# board_2.net
KiCad netlist of a schematic drawn in EAGLE
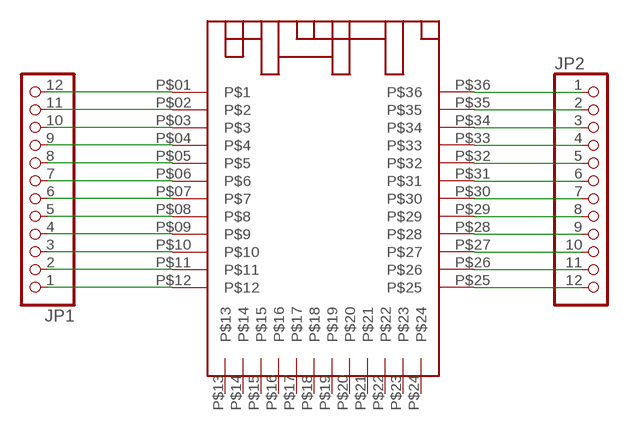
[diagram p0: schematic, sheet 1]

(export (version "E")
  (design (tool "Eeschema 10.0.6"))
  (components
    (comp (ref "JP1")
      (value "PINHD-1X12")
      (footprint "eagle-import:1X12")
      (libsource (lib "eagle-import") (part "PINHD-1X12"))
    )
    (comp (ref "JP2")
      (value "PINHD-1X12")
      (footprint "eagle-import:1X12")
      (libsource (lib "eagle-import") (part "PINHD-1X12"))
    )
    (comp (ref "U$1")
      (value "HZX_MODULE")
      (footprint "eagle-import:SMD_PAD_VERSION")
      (fields (field (name "AUTHOR") "Agam"))
      (libsource (lib "eagle-import") (part "HZX_MODULE"))
    )
  )
  (nets
    (net (code "1") (name "Net-(JP1-Pad1)") (class "Default")
      (node (ref "JP1") (pin "1") (pinfunction "1_1") (pintype "passive"))
      (node (ref "U$1") (pin "P$12") (pinfunction "P$12_P$12") (pintype "bidirectional"))
    )
    (net (code "2") (name "Net-(JP1-Pad2)") (class "Default")
      (node (ref "JP1") (pin "2") (pinfunction "2_2") (pintype "passive"))
      (node (ref "U$1") (pin "P$11") (pinfunction "P$11_P$11") (pintype "bidirectional"))
    )
    (net (code "3") (name "Net-(JP1-Pad3)") (class "Default")
      (node (ref "JP1") (pin "3") (pinfunction "3_3") (pintype "passive"))
      (node (ref "U$1") (pin "P$10") (pinfunction "P$10_P$10") (pintype "bidirectional"))
    )
    (net (code "4") (name "Net-(JP2-Pad1)") (class "Default")
      (node (ref "JP2") (pin "1") (pinfunction "1_1") (pintype "passive"))
      (node (ref "U$1") (pin "P$36") (pinfunction "P$36_P$36") (pintype "bidirectional"))
    )
    (net (code "5") (name "Net-(JP2-Pad2)") (class "Default")
      (node (ref "JP2") (pin "2") (pinfunction "2_2") (pintype "passive"))
      (node (ref "U$1") (pin "P$35") (pinfunction "P$35_P$35") (pintype "bidirectional"))
    )
    (net (code "6") (name "Net-(JP2-Pad3)") (class "Default")
      (node (ref "JP2") (pin "3") (pinfunction "3_3") (pintype "passive"))
      (node (ref "U$1") (pin "P$34") (pinfunction "P$34_P$34") (pintype "bidirectional"))
    )
    (net (code "7") (name "Net-(JP2-Pad4)") (class "Default")
      (node (ref "JP2") (pin "4") (pinfunction "4_4") (pintype "passive"))
      (node (ref "U$1") (pin "P$33") (pinfunction "P$33_P$33") (pintype "bidirectional"))
    )
    (net (code "8") (name "Net-(JP2-Pad5)") (class "Default")
      (node (ref "JP2") (pin "5") (pinfunction "5_5") (pintype "passive"))
      (node (ref "U$1") (pin "P$32") (pinfunction "P$32_P$32") (pintype "bidirectional"))
    )
    (net (code "9") (name "Net-(JP2-Pad6)") (class "Default")
      (node (ref "JP2") (pin "6") (pinfunction "6_6") (pintype "passive"))
      (node (ref "U$1") (pin "P$31") (pinfunction "P$31_P$31") (pintype "bidirectional"))
    )
    (net (code "10") (name "Net-(JP2-Pad7)") (class "Default")
      (node (ref "JP2") (pin "7") (pinfunction "7_7") (pintype "passive"))
      (node (ref "U$1") (pin "P$30") (pinfunction "P$30_P$30") (pintype "bidirectional"))
    )
    (net (code "11") (name "Net-(JP2-Pad8)") (class "Default")
      (node (ref "JP2") (pin "8") (pinfunction "8_8") (pintype "passive"))
      (node (ref "U$1") (pin "P$29") (pinfunction "P$29_P$29") (pintype "bidirectional"))
    )
    (net (code "12") (name "Net-(JP2-Pad9)") (class "Default")
      (node (ref "JP2") (pin "9") (pinfunction "9_9") (pintype "passive"))
      (node (ref "U$1") (pin "P$28") (pinfunction "P$28_P$28") (pintype "bidirectional"))
    )
    (net (code "13") (name "Net-(JP2-Pad10)") (class "Default")
      (node (ref "JP2") (pin "10") (pinfunction "10_10") (pintype "passive"))
      (node (ref "U$1") (pin "P$27") (pinfunction "P$27_P$27") (pintype "bidirectional"))
    )
    (net (code "14") (name "Net-(JP2-Pad11)") (class "Default")
      (node (ref "JP2") (pin "11") (pinfunction "11_11") (pintype "passive"))
      (node (ref "U$1") (pin "P$26") (pinfunction "P$26_P$26") (pintype "bidirectional"))
    )
    (net (code "15") (name "Net-(JP2-Pad12)") (class "Default")
      (node (ref "JP2") (pin "12") (pinfunction "12_12") (pintype "passive"))
      (node (ref "U$1") (pin "P$25") (pinfunction "P$25_P$25") (pintype "bidirectional"))
    )
    (net (code "16") (name "Net-(U$1-P$1)") (class "Default")
      (node (ref "JP1") (pin "12") (pinfunction "12_12") (pintype "passive"))
      (node (ref "U$1") (pin "P$01") (pinfunction "P$1_P$01") (pintype "bidirectional"))
    )
    (net (code "17") (name "Net-(U$1-P$2)") (class "Default")
      (node (ref "JP1") (pin "11") (pinfunction "11_11") (pintype "passive"))
      (node (ref "U$1") (pin "P$02") (pinfunction "P$2_P$02") (pintype "bidirectional"))
    )
    (net (code "18") (name "Net-(U$1-P$3)") (class "Default")
      (node (ref "JP1") (pin "10") (pinfunction "10_10") (pintype "passive"))
      (node (ref "U$1") (pin "P$03") (pinfunction "P$3_P$03") (pintype "bidirectional"))
    )
    (net (code "19") (name "Net-(U$1-P$4)") (class "Default")
      (node (ref "JP1") (pin "9") (pinfunction "9_9") (pintype "passive"))
      (node (ref "U$1") (pin "P$04") (pinfunction "P$4_P$04") (pintype "bidirectional"))
    )
    (net (code "20") (name "Net-(U$1-P$5)") (class "Default")
      (node (ref "JP1") (pin "8") (pinfunction "8_8") (pintype "passive"))
      (node (ref "U$1") (pin "P$05") (pinfunction "P$5_P$05") (pintype "bidirectional"))
    )
    (net (code "21") (name "Net-(U$1-P$6)") (class "Default")
      (node (ref "JP1") (pin "7") (pinfunction "7_7") (pintype "passive"))
      (node (ref "U$1") (pin "P$06") (pinfunction "P$6_P$06") (pintype "bidirectional"))
    )
    (net (code "22") (name "Net-(U$1-P$7)") (class "Default")
      (node (ref "JP1") (pin "6") (pinfunction "6_6") (pintype "passive"))
      (node (ref "U$1") (pin "P$07") (pinfunction "P$7_P$07") (pintype "bidirectional"))
    )
    (net (code "23") (name "Net-(U$1-P$8)") (class "Default")
      (node (ref "JP1") (pin "5") (pinfunction "5_5") (pintype "passive"))
      (node (ref "U$1") (pin "P$08") (pinfunction "P$8_P$08") (pintype "bidirectional"))
    )
    (net (code "24") (name "Net-(U$1-P$9)") (class "Default")
      (node (ref "JP1") (pin "4") (pinfunction "4_4") (pintype "passive"))
      (node (ref "U$1") (pin "P$09") (pinfunction "P$9_P$09") (pintype "bidirectional"))
    )
    (net (code "25") (name "unconnected-(U$1-PadP$13)") (class "Default")
      (node (ref "U$1") (pin "P$13") (pinfunction "P$13_P$13") (pintype "bidirectional"))
    )
    (net (code "26") (name "unconnected-(U$1-PadP$14)") (class "Default")
      (node (ref "U$1") (pin "P$14") (pinfunction "P$14_P$14") (pintype "bidirectional"))
    )
    (net (code "27") (name "unconnected-(U$1-PadP$15)") (class "Default")
      (node (ref "U$1") (pin "P$15") (pinfunction "P$15_P$15") (pintype "bidirectional"))
    )
    (net (code "28") (name "unconnected-(U$1-PadP$16)") (class "Default")
      (node (ref "U$1") (pin "P$16") (pinfunction "P$16_P$16") (pintype "bidirectional"))
    )
    (net (code "29") (name "unconnected-(U$1-PadP$17)") (class "Default")
      (node (ref "U$1") (pin "P$17") (pinfunction "P$17_P$17") (pintype "bidirectional"))
    )
    (net (code "30") (name "unconnected-(U$1-PadP$18)") (class "Default")
      (node (ref "U$1") (pin "P$18") (pinfunction "P$18_P$18") (pintype "bidirectional"))
    )
    (net (code "31") (name "unconnected-(U$1-PadP$19)") (class "Default")
      (node (ref "U$1") (pin "P$19") (pinfunction "P$19_P$19") (pintype "bidirectional"))
    )
    (net (code "32") (name "unconnected-(U$1-PadP$20)") (class "Default")
      (node (ref "U$1") (pin "P$20") (pinfunction "P$20_P$20") (pintype "bidirectional"))
    )
    (net (code "33") (name "unconnected-(U$1-PadP$21)") (class "Default")
      (node (ref "U$1") (pin "P$21") (pinfunction "P$21_P$21") (pintype "bidirectional"))
    )
    (net (code "34") (name "unconnected-(U$1-PadP$22)") (class "Default")
      (node (ref "U$1") (pin "P$22") (pinfunction "P$22_P$22") (pintype "bidirectional"))
    )
    (net (code "35") (name "unconnected-(U$1-PadP$23)") (class "Default")
      (node (ref "U$1") (pin "P$23") (pinfunction "P$23_P$23") (pintype "bidirectional"))
    )
    (net (code "36") (name "unconnected-(U$1-PadP$24)") (class "Default")
      (node (ref "U$1") (pin "P$24") (pinfunction "P$24_P$24") (pintype "bidirectional"))
    )
  )
)
